# HTU21D_Breakout.net
KiCad netlist of a schematic drawn in EAGLE
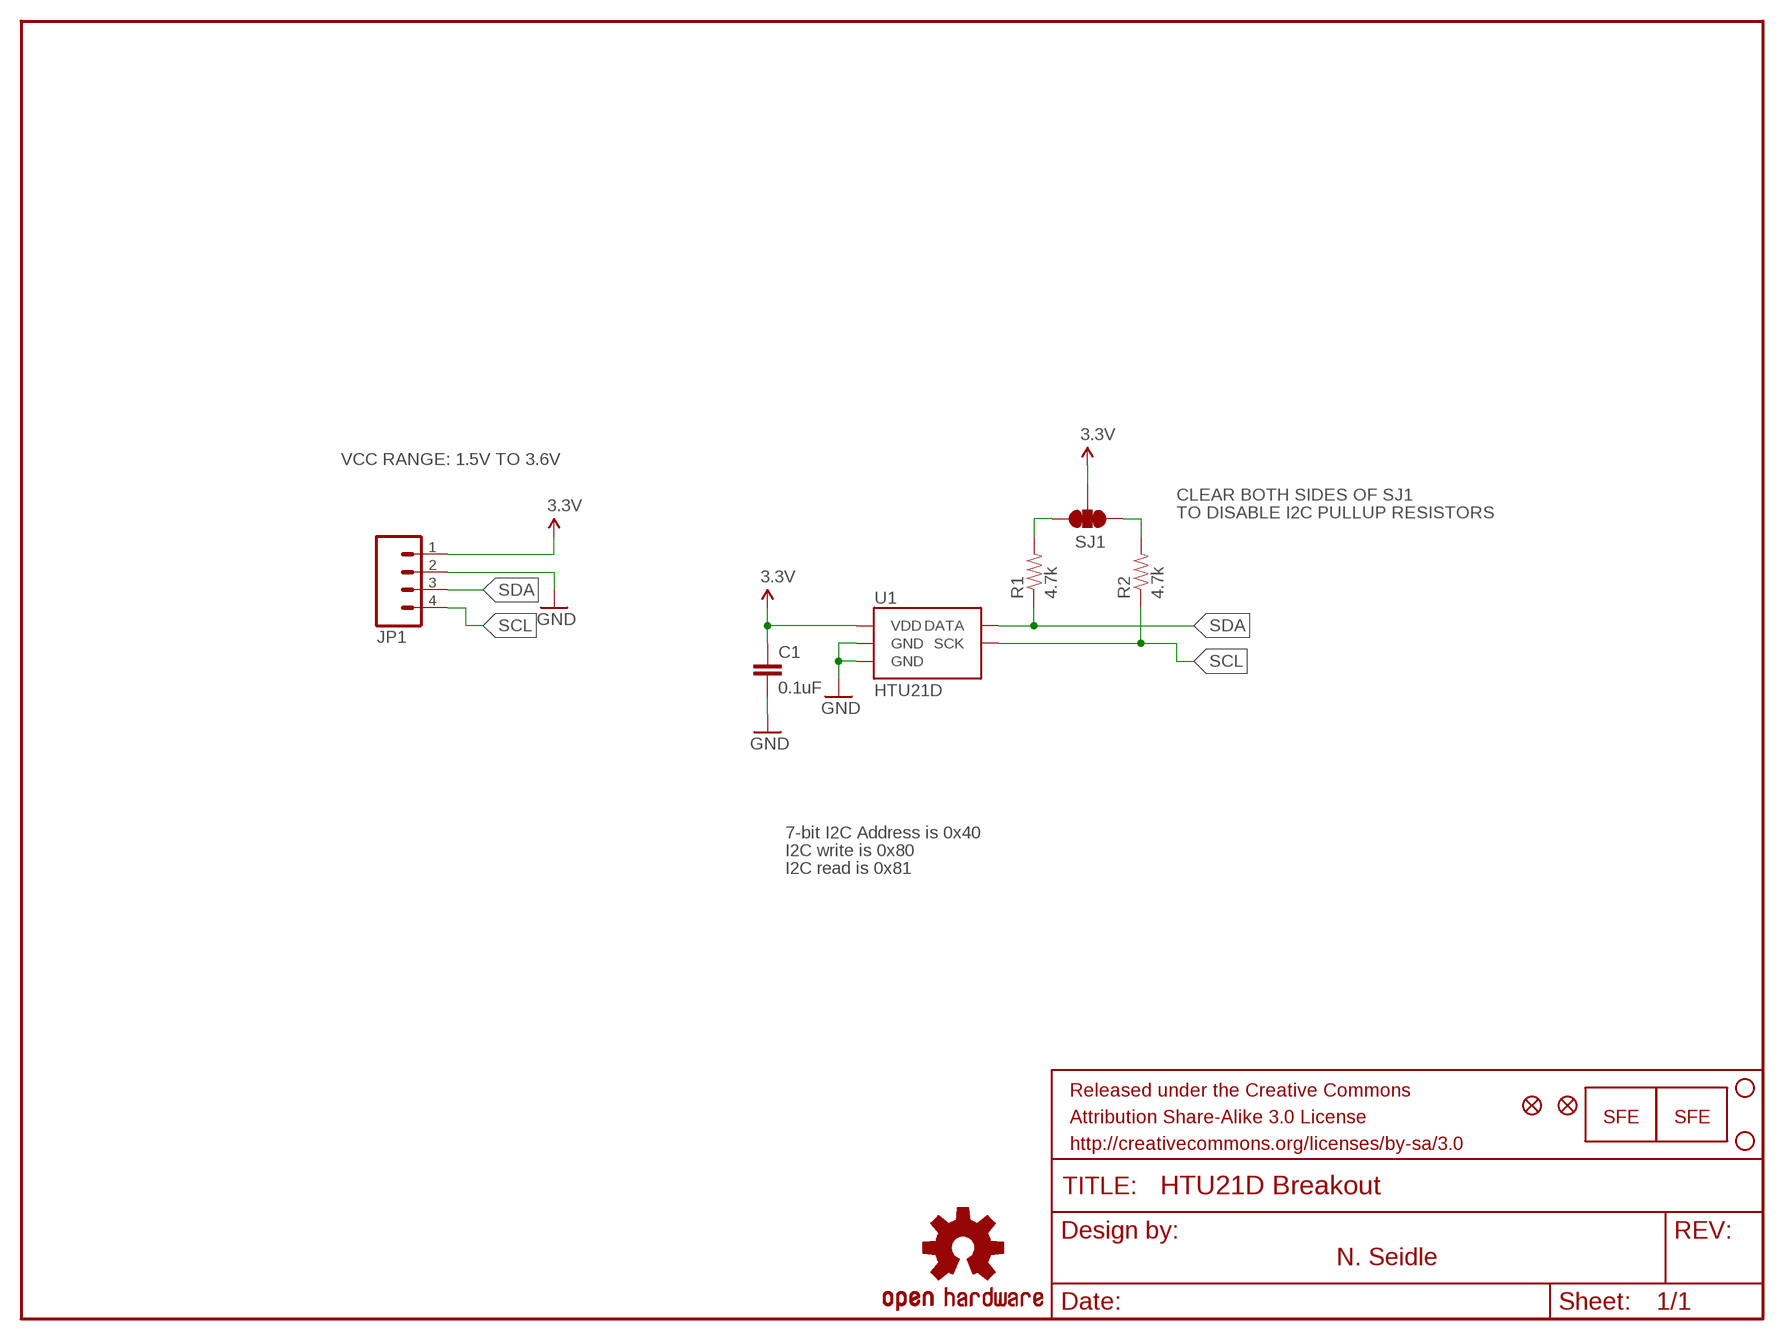
[diagram p0: schematic, sheet 1]

(export (version "E")
  (design (tool "Eeschema 10.0.6"))
  (components
    (comp (ref "C1")
      (value "0.1uF")
      (footprint "eagle-import:0603-CAP")
      (libsource (lib "eagle-import") (part "CAP0603-CAP"))
    )
    (comp (ref "FRAME2")
      (value "FRAME-LETTER")
      (footprint "eagle-import:CREATIVE_COMMONS")
      (libsource (lib "eagle-import") (part "FRAME-LETTER"))
    )
    (comp (ref "JP1")
      (value "M04PTH")
      (footprint "eagle-import:1X04")
      (libsource (lib "eagle-import") (part "M04PTH"))
    )
    (comp (ref "JP2")
      (value "LOGO-SFENW2")
      (footprint "eagle-import:SFE-NEW-WEB")
      (libsource (lib "eagle-import") (part "SparkFun-Aesthetics_LOGO-SFENW2"))
    )
    (comp (ref "JP3")
      (value "FIDUCIALUFIDUCIAL")
      (footprint "eagle-import:MICRO-FIDUCIAL")
      (libsource (lib "eagle-import") (part "FIDUCIALUFIDUCIAL"))
    )
    (comp (ref "JP4")
      (value "FIDUCIALUFIDUCIAL")
      (footprint "eagle-import:MICRO-FIDUCIAL")
      (libsource (lib "eagle-import") (part "FIDUCIALUFIDUCIAL"))
    )
    (comp (ref "LOGO1")
      (value "LOGO-SFESK")
      (footprint "eagle-import:SFE-LOGO-FLAME")
      (libsource (lib "eagle-import") (part "LOGO-SFESK"))
    )
    (comp (ref "LOGO2")
      (value "OSHW-LOGOS")
      (footprint "eagle-import:OSHW-LOGO-S")
      (libsource (lib "eagle-import") (part "OSHW-LOGOS"))
    )
    (comp (ref "R1")
      (value "4.7k")
      (footprint "eagle-import:0603-RES")
      (libsource (lib "eagle-import") (part "RESISTOR0603-RES"))
    )
    (comp (ref "R2")
      (value "4.7k")
      (footprint "eagle-import:0603-RES")
      (libsource (lib "eagle-import") (part "RESISTOR0603-RES"))
    )
    (comp (ref "SJ1")
      (value "SOLDERJUMPER_2WAYPASTE1&2&3")
      (footprint "eagle-import:SJ_3_PASTE1&2&3")
      (libsource (lib "eagle-import") (part "SOLDERJUMPER_2WAYPASTE1&2&3"))
    )
    (comp (ref "STANDOFF1")
      (value "STAND-OFF")
      (footprint "eagle-import:STAND-OFF")
      (libsource (lib "eagle-import") (part "STAND-OFF"))
    )
    (comp (ref "STANDOFF2")
      (value "STAND-OFF")
      (footprint "eagle-import:STAND-OFF")
      (libsource (lib "eagle-import") (part "STAND-OFF"))
    )
    (comp (ref "U1")
      (value "HTU21D")
      (footprint "eagle-import:HTU21D")
      (libsource (lib "eagle-import") (part "HTU21DSMD"))
    )
  )
  (nets
    (net (code "1") (name "3.3V") (class "Default")
      (node (ref "C1") (pin "1") (pinfunction "1_1") (pintype "passive"))
      (node (ref "JP1") (pin "1") (pinfunction "1_1") (pintype "passive"))
      (node (ref "SJ1") (pin "2") (pinfunction "2_2") (pintype "passive"))
      (node (ref "U1") (pin "VDD") (pinfunction "VDD_VDD") (pintype "power_in"))
    )
    (net (code "2") (name "GND") (class "Default")
      (node (ref "C1") (pin "2") (pinfunction "2_2") (pintype "passive"))
      (node (ref "JP1") (pin "2") (pinfunction "2_2") (pintype "passive"))
      (node (ref "U1") (pin "7") (pinfunction "GND_7") (pintype "power_in"))
      (node (ref "U1") (pin "GND") (pinfunction "GND_GND") (pintype "power_in"))
    )
    (net (code "3") (name "Net-(R1-Pad2)") (class "Default")
      (node (ref "R1") (pin "2") (pinfunction "2_2") (pintype "passive"))
      (node (ref "SJ1") (pin "3") (pinfunction "3_3") (pintype "passive"))
    )
    (net (code "4") (name "Net-(R2-Pad2)") (class "Default")
      (node (ref "R2") (pin "2") (pinfunction "2_2") (pintype "passive"))
      (node (ref "SJ1") (pin "1") (pinfunction "1_1") (pintype "passive"))
    )
    (net (code "5") (name "SCL") (class "Default")
      (node (ref "JP1") (pin "4") (pinfunction "4_4") (pintype "passive"))
      (node (ref "R2") (pin "1") (pinfunction "1_1") (pintype "passive"))
      (node (ref "U1") (pin "SCK") (pinfunction "SCK_SCK") (pintype "input"))
    )
    (net (code "6") (name "SDA") (class "Default")
      (node (ref "JP1") (pin "3") (pinfunction "3_3") (pintype "passive"))
      (node (ref "R1") (pin "1") (pinfunction "1_1") (pintype "passive"))
      (node (ref "U1") (pin "DATA") (pinfunction "DATA_DATA") (pintype "bidirectional"))
    )
  )
)
